# Final.net
KiCad netlist of a schematic drawn in EAGLE
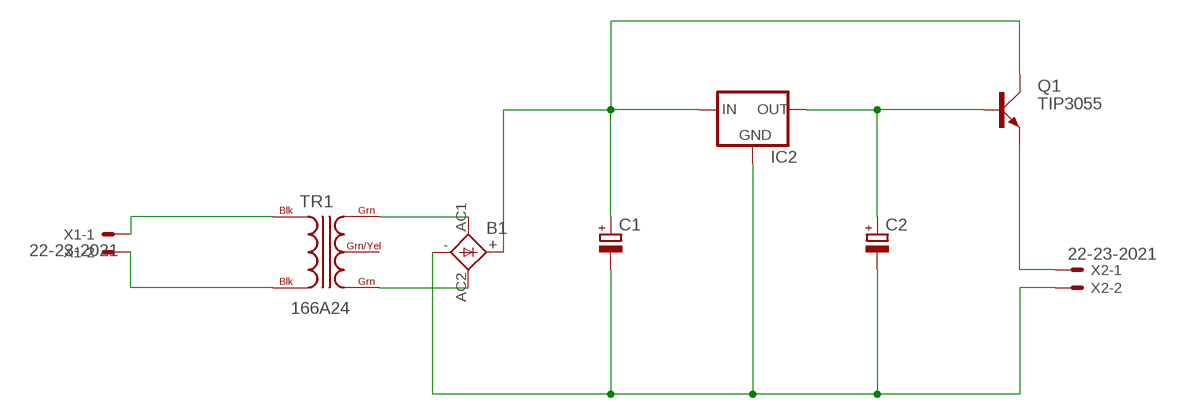
[diagram p0: schematic, sheet 1]

(export (version "E")
  (design (tool "Eeschema 10.0.6"))
  (components
    (comp (ref "B1")
      (value "FB32")
      (footprint "eagle-import:FB32")
      (libsource (lib "eagle-import") (part "FB32"))
    )
    (comp (ref "C1")
      (value "CPOL-EUE7.5-16")
      (footprint "eagle-import:E7,5-16")
      (libsource (lib "eagle-import") (part "CPOL-EUE7.5-16"))
    )
    (comp (ref "C2")
      (value "CPOL-EUE3.5-8")
      (footprint "eagle-import:E3,5-8")
      (libsource (lib "eagle-import") (part "CPOL-EUE3.5-8"))
    )
    (comp (ref "IC2")
      (value "78XXL")
      (footprint "eagle-import:78XXL")
      (libsource (lib "eagle-import") (part "78XXL"))
    )
    (comp (ref "Q1")
      (value "TIP3055")
      (footprint "eagle-import:TOP3AV")
      (libsource (lib "eagle-import") (part "TIP3055"))
    )
    (comp (ref "TR1")
      (value "166A24")
      (footprint "eagle-import:C2H")
      (libsource (lib "eagle-import") (part "166A24"))
    )
    (comp (ref "X1")
      (value "22-23-2021")
      (footprint "eagle-import:22-23-2021")
      (fields (field (name "MF") "MOLEX"))
      (libsource (lib "eagle-import") (part "22-23-2021"))
    )
    (comp (ref "X2")
      (value "22-23-2021")
      (footprint "eagle-import:22-23-2021")
      (fields (field (name "MF") "MOLEX"))
      (libsource (lib "eagle-import") (part "22-23-2021"))
    )
  )
  (nets
    (net (code "1") (name "Net-(B1-Pad+)") (class "Default")
      (node (ref "B1") (pin "+") (pinfunction "+_+") (pintype "passive"))
      (node (ref "C1") (pin "+") (pinfunction "+_+") (pintype "passive"))
      (node (ref "IC2") (pin "IN") (pinfunction "IN_IN") (pintype "input"))
      (node (ref "Q1") (pin "C") (pinfunction "C_C") (pintype "passive"))
    )
    (net (code "2") (name "Net-(B1-PadAC1)") (class "Default")
      (node (ref "B1") (pin "AC1") (pinfunction "AC1_AC1") (pintype "passive"))
      (node (ref "TR1") (pin "GRN@1") (pinfunction "GRN_GRN@1") (pintype "passive"))
    )
    (net (code "3") (name "Net-(B1-PadAC2)") (class "Default")
      (node (ref "B1") (pin "AC2") (pinfunction "AC2_AC2") (pintype "passive"))
      (node (ref "TR1") (pin "GRN@2") (pinfunction "GRN_GRN@2") (pintype "passive"))
    )
    (net (code "4") (name "Net-(C2-Pad+)") (class "Default")
      (node (ref "C2") (pin "+") (pinfunction "+_+") (pintype "passive"))
      (node (ref "IC2") (pin "OUT") (pinfunction "OUT_OUT") (pintype "passive"))
      (node (ref "Q1") (pin "B") (pinfunction "B_B") (pintype "passive"))
    )
    (net (code "5") (name "Net-(X1A-S)") (class "Default")
      (node (ref "TR1") (pin "BLK@1") (pinfunction "BLK_BLK@1") (pintype "passive"))
      (node (ref "X1") (pin "1") (pinfunction "S_1") (pintype "passive"))
    )
    (net (code "6") (name "Net-(X1B-S)") (class "Default")
      (node (ref "TR1") (pin "BLK@2") (pinfunction "BLK_BLK@2") (pintype "passive"))
      (node (ref "X1") (pin "2") (pinfunction "S_2") (pintype "passive"))
    )
    (net (code "7") (name "Net-(X2A-S)") (class "Default")
      (node (ref "Q1") (pin "E") (pinfunction "E_E") (pintype "passive"))
      (node (ref "X2") (pin "1") (pinfunction "S_1") (pintype "passive"))
    )
    (net (code "8") (name "Net-(X2B-S)") (class "Default")
      (node (ref "B1") (pin "-") (pinfunction "-_-") (pintype "passive"))
      (node (ref "C1") (pin "-") (pinfunction "-_-") (pintype "passive"))
      (node (ref "C2") (pin "-") (pinfunction "-_-") (pintype "passive"))
      (node (ref "IC2") (pin "GND") (pinfunction "GND_GND") (pintype "input"))
      (node (ref "X2") (pin "2") (pinfunction "S_2") (pintype "passive"))
    )
    (net (code "9") (name "unconnected-(TR1-PadGRN{slash}YEL)") (class "Default")
      (node (ref "TR1") (pin "GRN/YEL") (pinfunction "GRN/YEL_GRN/YEL") (pintype "passive"))
    )
  )
)
